# Rotary_Encoder_Breakout_Sch.net
KiCad netlist of a schematic drawn in Altium Designer
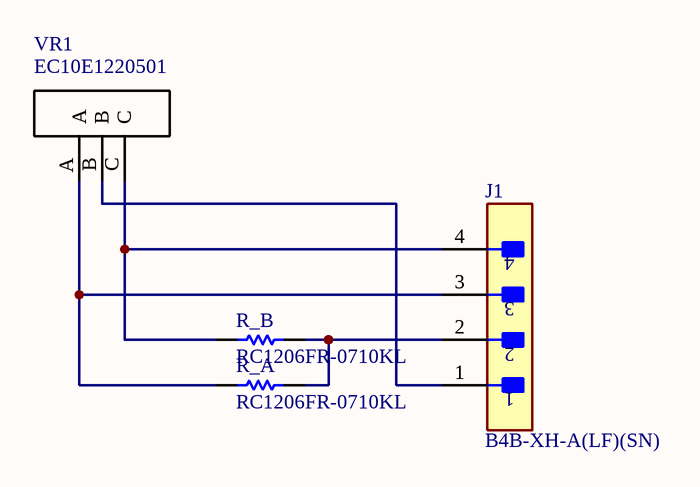
[diagram p0: Rotary_Encoder_Breakout_Sch.SchDoc]

(export (version "E")
  (design (tool "Eeschema 10.0.6"))
  (components
    (comp (ref "J1")
      (value "B4B-XH-A(LF)(SN)")
      (footprint "FP-B4B-XH-A_LF_SN-MFG")
      (description "CONN HEADER VERT 4POS 2.5MM")
      (libsource (lib "Altium Content Vault") (part "299a8cea1bdcbc3624fe62c390fa72c"))
    )
    (comp (ref "R_A")
      (value "RC1206FR-0710KL")
      (footprint "RESC3116X65X40ML10T20")
      (description "Chip Resistor, 10 KOhm, +/- 1%, 0.25 W, -55 to 155 degC, 1206 (3216 Metric), RoHS, Tape and Reel")
      (fields (field (name "TOLERANCE") "1%") (field (name "MANUFACTURER") "Yageo"))
      (libsource (lib "Altium Content Vault") (part "RES-2"))
    )
    (comp (ref "R_B")
      (value "RC1206FR-0710KL")
      (footprint "RESC3116X65X40ML10T20")
      (description "Chip Resistor, 10 KOhm, +/- 1%, 0.25 W, -55 to 155 degC, 1206 (3216 Metric), RoHS, Tape and Reel")
      (fields (field (name "TOLERANCE") "1%") (field (name "MANUFACTURER") "Yageo"))
      (libsource (lib "Altium Content Vault") (part "RES-2"))
    )
    (comp (ref "VR1")
      (value "EC10E1220501")
      (footprint "*TRIM_EC10E1220501_EC10E1220501(Primary)")
      (fields (field (name "MF") "ALPS"))
      (libsource (lib "EC10E1220501") (part "EC10E1220501"))
    )
  )
  (nets
    (net (code "1") (name "Net-(J1-Pad1)") (class "Default")
      (node (ref "J1") (pin "1") (pinfunction "1_1") (pintype "passive"))
      (node (ref "VR1") (pin "B") (pinfunction "B_B") (pintype "passive"))
    )
    (net (code "2") (name "Net-(J1-Pad2)") (class "Default")
      (node (ref "J1") (pin "2") (pinfunction "2_2") (pintype "passive"))
      (node (ref "R_A") (pin "1") (pinfunction "1_1") (pintype "passive"))
      (node (ref "R_B") (pin "1") (pinfunction "1_1") (pintype "passive"))
    )
    (net (code "3") (name "Net-(J1-Pad3)") (class "Default")
      (node (ref "J1") (pin "3") (pinfunction "3_3") (pintype "passive"))
      (node (ref "R_A") (pin "2") (pinfunction "2_2") (pintype "passive"))
      (node (ref "VR1") (pin "A") (pinfunction "A_A") (pintype "passive"))
    )
    (net (code "4") (name "Net-(J1-Pad4)") (class "Default")
      (node (ref "J1") (pin "4") (pinfunction "4_4") (pintype "passive"))
      (node (ref "R_B") (pin "2") (pinfunction "2_2") (pintype "passive"))
      (node (ref "VR1") (pin "C") (pinfunction "C_C") (pintype "passive"))
    )
  )
)
